# CW308_Clock.net
KiCad netlist of a schematic drawn in Altium Designer
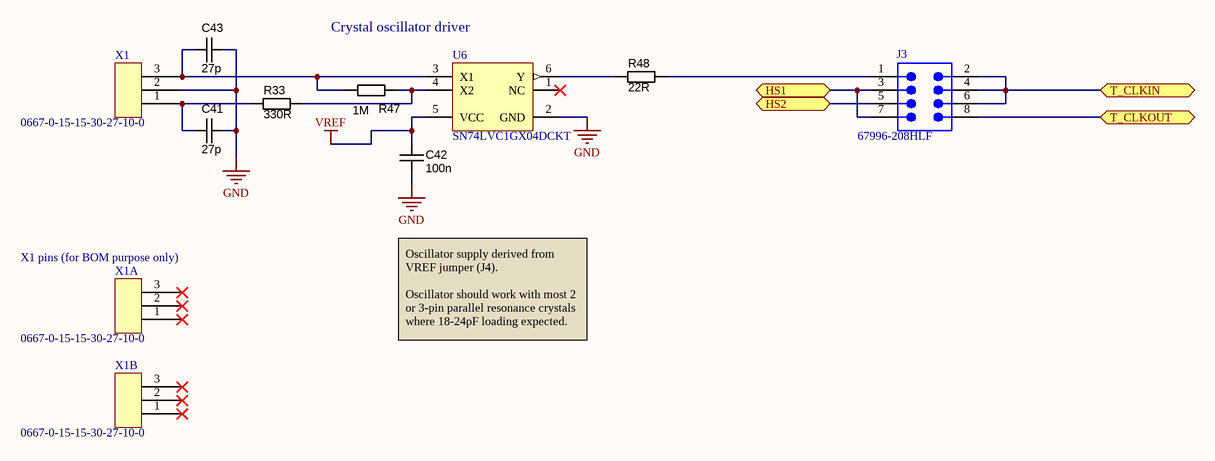
[diagram p0: CW308_Clock.SchDoc]

(export (version "E")
  (design (tool "Eeschema 10.0.6"))
  (components
    (comp (ref "C41")
      (value "27p")
      (footprint "CAPC1608X90N")
      (description "Capacitor SMD Cer 27pF 1% 100V NP0 0603")
      (fields (field (name "TOLERANCE") "±1%"))
      (libsource (lib "PBL - Capacitors") (part "CAPC_27p_0603_NP0_100V_1%"))
    )
    (comp (ref "C42")
      (value "100n")
      (footprint "CAPC1608X90N")
      (description "Capacitor SMD Cer 100nF 10% 50V X7R 0603")
      (fields (field (name "TOLERANCE") "±10%") (field (name "Comment") "approved sub OK"))
      (libsource (lib "PBL - Capacitors") (part "CAPC_100n_0603_X7R_50V_10%"))
    )
    (comp (ref "C43")
      (value "27p")
      (footprint "CAPC1608X90N")
      (description "Capacitor SMD Cer 27pF 1% 100V NP0 0603")
      (fields (field (name "TOLERANCE") "±1%"))
      (libsource (lib "PBL - Capacitors") (part "CAPC_27p_0603_NP0_100V_1%"))
    )
    (comp (ref "J3")
      (value "67996-208HLF")
      (footprint "SMTC-MTSW-104-12-X-D-006")
      (fields (field (name "MANUFACTURER") "Amphenol FCI"))
      (libsource (lib "Altium Content Vault") (part "CMP-1024-00110-1"))
    )
    (comp (ref "R33")
      (value "330R")
      (footprint "RESC1608X55N")
      (description "Resistor SMD chip 330 Ohm 0.1W 5% 0603")
      (fields (field (name "TOLERANCE") "±5%") (field (name "Comment") "Thick Film"))
      (libsource (lib "PBL - Resistors") (part "RES_330R_0603_5%"))
    )
    (comp (ref "R47")
      (value "1M")
      (footprint "RESC1608X55N")
      (description "Resistor SMD chip 1M Ohm 0.1W 5% 0603")
      (fields (field (name "TOLERANCE") "±5%") (field (name "Comment") "Thick Film"))
      (libsource (lib "PBL - Resistors") (part "RES_1M_0603_5%"))
    )
    (comp (ref "R48")
      (value "22R")
      (footprint "RESC1608X55N")
      (description "Resistor SMD chip 22 Ohm 0.1W 5% 0603")
      (fields (field (name "TOLERANCE") "±5%") (field (name "Comment") "Thick Film"))
      (libsource (lib "PBL - Resistors") (part "RES_22R_0603_5%"))
    )
    (comp (ref "U6")
      (value "SN74LVC1GX04DCKT")
      (footprint "DCK0006A_L")
      (description "Crystal Oscillator Driver, DCK0006A, SMALL T&R")
      (fields
        (field (name "MANUFACTURER") "Texas Instruments")
        (field (name "GENERIC PART NUMBER") "SN74LVC1GX04")
      )
      (libsource (lib "Altium Content Vault") (part "CMP-0859-00485-3"))
    )
    (comp (ref "X1")
      (value "0667-0-15-15-30-27-10-0")
      (footprint "HC49U_SOCKET")
      (description "XTAL Holder built using 3x 0667-0-15-15-30-27-10-0")
      (libsource (lib "NewAE_AltiumLib") (part "XTALHOLDER_49US"))
    )
    (comp (ref "X1A")
      (value "0667-0-15-15-30-27-10-0")
      (footprint "HC49U_SOCKET")
      (description "XTAL Holder built using 3x 0667-0-15-15-30-27-10-0")
      (libsource (lib "NewAE_AltiumLib") (part "XTALHOLDER_49US"))
    )
    (comp (ref "X1B")
      (value "0667-0-15-15-30-27-10-0")
      (footprint "HC49U_SOCKET")
      (description "XTAL Holder built using 3x 0667-0-15-15-30-27-10-0")
      (libsource (lib "NewAE_AltiumLib") (part "XTALHOLDER_49US"))
    )
  )
  (nets
    (net (code "1") (name "/HS1") (class "Default")
      (node (ref "J3") (pin "3") (pinfunction "3_3") (pintype "passive"))
      (node (ref "J3") (pin "7") (pinfunction "7_7") (pintype "passive"))
    )
    (net (code "2") (name "/HS2") (class "Default")
      (node (ref "J3") (pin "5") (pinfunction "5_5") (pintype "passive"))
    )
    (net (code "3") (name "/T_CLKIN") (class "Default")
      (node (ref "J3") (pin "2") (pinfunction "2_2") (pintype "passive"))
      (node (ref "J3") (pin "4") (pinfunction "4_4") (pintype "passive"))
      (node (ref "J3") (pin "6") (pinfunction "6_6") (pintype "passive"))
    )
    (net (code "4") (name "/T_CLKOUT") (class "Default")
      (node (ref "J3") (pin "8") (pinfunction "8_8") (pintype "passive"))
    )
    (net (code "5") (name "GND") (class "Default")
      (node (ref "C41") (pin "2") (pintype "passive"))
      (node (ref "C42") (pin "2") (pintype "passive"))
      (node (ref "C43") (pin "2") (pintype "passive"))
      (node (ref "U6") (pin "2") (pinfunction "GND_2") (pintype "power_in"))
      (node (ref "X1") (pin "2") (pinfunction "2_2") (pintype "passive"))
    )
    (net (code "6") (name "Net-(C41-Pad1)") (class "Default")
      (node (ref "C41") (pin "1") (pintype "passive"))
      (node (ref "R33") (pin "1") (pinfunction "1_1") (pintype "passive"))
      (node (ref "X1") (pin "1") (pinfunction "1_1") (pintype "passive"))
    )
    (net (code "7") (name "Net-(J3-Pad1)") (class "Default")
      (node (ref "J3") (pin "1") (pinfunction "1_1") (pintype "passive"))
      (node (ref "R48") (pin "2") (pinfunction "2_2") (pintype "passive"))
    )
    (net (code "8") (name "Net-(U6-X1)") (class "Default")
      (node (ref "C43") (pin "1") (pintype "passive"))
      (node (ref "R47") (pin "1") (pinfunction "1_1") (pintype "passive"))
      (node (ref "U6") (pin "3") (pinfunction "X1_3") (pintype "passive"))
      (node (ref "X1") (pin "3") (pinfunction "3_3") (pintype "passive"))
    )
    (net (code "9") (name "Net-(U6-X2)") (class "Default")
      (node (ref "R33") (pin "2") (pinfunction "2_2") (pintype "passive"))
      (node (ref "R47") (pin "2") (pinfunction "2_2") (pintype "passive"))
      (node (ref "U6") (pin "4") (pinfunction "X2_4") (pintype "passive"))
    )
    (net (code "10") (name "Net-(U6-Y)") (class "Default")
      (node (ref "R48") (pin "1") (pinfunction "1_1") (pintype "passive"))
      (node (ref "U6") (pin "6") (pinfunction "Y_6") (pintype "output"))
    )
    (net (code "11") (name "VREF") (class "Default")
      (node (ref "C42") (pin "1") (pintype "passive"))
      (node (ref "U6") (pin "5") (pinfunction "VCC_5") (pintype "power_in"))
    )
    (net (code "12") (name "unconnected-(U6-NC-Pad1)") (class "Default")
      (node (ref "U6") (pin "1") (pinfunction "NC_1") (pintype "passive+no_connect"))
    )
    (net (code "13") (name "unconnected-(X1A-Pad1)") (class "Default")
      (node (ref "X1A") (pin "1") (pinfunction "1_1") (pintype "passive+no_connect"))
    )
    (net (code "14") (name "unconnected-(X1A-Pad2)") (class "Default")
      (node (ref "X1A") (pin "2") (pinfunction "2_2") (pintype "passive+no_connect"))
    )
    (net (code "15") (name "unconnected-(X1A-Pad3)") (class "Default")
      (node (ref "X1A") (pin "3") (pinfunction "3_3") (pintype "passive+no_connect"))
    )
    (net (code "16") (name "unconnected-(X1B-Pad1)") (class "Default")
      (node (ref "X1B") (pin "1") (pinfunction "1_1") (pintype "passive+no_connect"))
    )
    (net (code "17") (name "unconnected-(X1B-Pad2)") (class "Default")
      (node (ref "X1B") (pin "2") (pinfunction "2_2") (pintype "passive+no_connect"))
    )
    (net (code "18") (name "unconnected-(X1B-Pad3)") (class "Default")
      (node (ref "X1B") (pin "3") (pinfunction "3_3") (pintype "passive+no_connect"))
    )
  )
)
